# main.net
KiCad netlist of a schematic drawn in Altium Designer
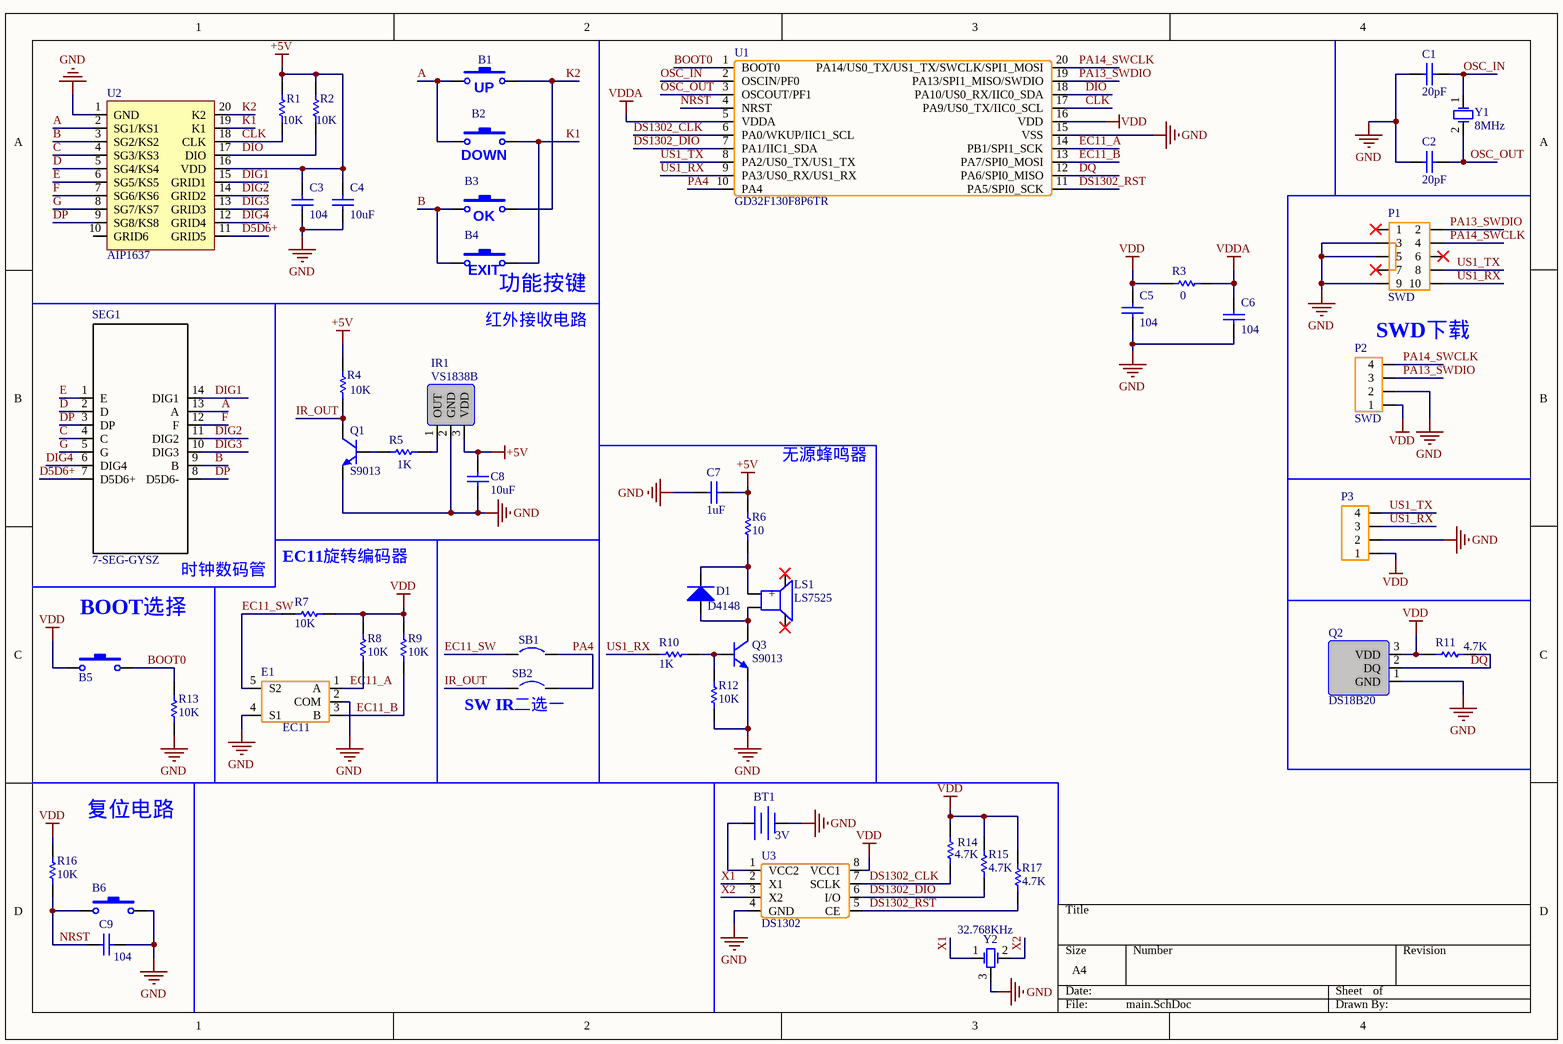
[diagram p0: main.SchDoc]

(export (version "E")
  (design (tool "Eeschema 10.0.6"))
  (components
    (comp (ref "B1")
      (value "用户按钮")
      (footprint "SW-SMD_L6.0-W3.5-LS8.0")
      (description "轻触按钮 - Switch")
      (fields (field (name "PUBLISHER") "Altium Limited"))
      (libsource (lib "ZSF-90") (part "Button"))
    )
    (comp (ref "B2")
      (value "用户按钮")
      (footprint "SW-SMD_L6.0-W3.5-LS8.0")
      (description "轻触按钮 - Switch")
      (fields (field (name "PUBLISHER") "Altium Limited"))
      (libsource (lib "ZSF-90") (part "Button"))
    )
    (comp (ref "B3")
      (value "用户按钮")
      (footprint "SW-SMD_L6.0-W3.5-LS8.0")
      (description "轻触按钮 - Switch")
      (fields (field (name "PUBLISHER") "Altium Limited"))
      (libsource (lib "ZSF-90") (part "Button"))
    )
    (comp (ref "B4")
      (value "用户按钮")
      (footprint "SW-SMD_L6.0-W3.5-LS8.0")
      (description "轻触按钮 - Switch")
      (fields (field (name "PUBLISHER") "Altium Limited"))
      (libsource (lib "ZSF-90") (part "Button"))
    )
    (comp (ref "B5")
      (value "复位按钮")
      (footprint "SW-SMD_L6.0-W3.5-LS8.0")
      (description "轻触按钮 - Switch")
      (fields (field (name "PUBLISHER") "Altium Limited"))
      (libsource (lib "ZSF-90") (part "Button"))
    )
    (comp (ref "B6")
      (value "复位按钮")
      (footprint "SW-SMD_L6.0-W3.5-LS8.0")
      (description "轻触按钮 - Switch")
      (fields (field (name "PUBLISHER") "Altium Limited"))
      (libsource (lib "ZSF-90") (part "Button"))
    )
    (comp (ref "BT1")
      (value "3V")
      (footprint "BAT-SMD_CR1220-2")
      (description "电池")
      (libsource (lib "ZSF-90") (part "Battery"))
    )
    (comp (ref "C1")
      (value "20pF")
      (footprint "C0603")
      (description "无极性电容")
      (fields (field (name "Comment") "Cap") (field (name "PUBLISHER") "信念D力量"))
      (libsource (lib "ZSF-90") (part "Cap"))
    )
    (comp (ref "C2")
      (value "20pF")
      (footprint "C0603")
      (description "无极性电容")
      (fields (field (name "Comment") "Cap") (field (name "PUBLISHER") "信念D力量"))
      (libsource (lib "ZSF-90") (part "Cap"))
    )
    (comp (ref "C3")
      (value "104")
      (footprint "C0603")
      (description "无极性电容")
      (fields (field (name "Comment") "Cap") (field (name "PUBLISHER") "信念D力量"))
      (libsource (lib "ZSF-90") (part "Cap"))
    )
    (comp (ref "C4")
      (value "10uF")
      (footprint "C1812")
      (description "无极性电容")
      (fields (field (name "Comment") "Cap") (field (name "PUBLISHER") "信念D力量"))
      (libsource (lib "ZSF-90") (part "Cap"))
    )
    (comp (ref "C5")
      (value "104")
      (footprint "C0603")
      (description "无极性电容")
      (fields (field (name "Comment") "Cap") (field (name "PUBLISHER") "信念D力量"))
      (libsource (lib "ZSF-90") (part "Cap"))
    )
    (comp (ref "C6")
      (value "104")
      (footprint "C0603")
      (description "无极性电容")
      (fields (field (name "Comment") "Cap") (field (name "PUBLISHER") "信念D力量"))
      (libsource (lib "ZSF-90") (part "Cap"))
    )
    (comp (ref "C7")
      (value "1uF")
      (footprint "C1206")
      (description "无极性电容")
      (fields (field (name "Comment") "Cap") (field (name "PUBLISHER") "信念D力量"))
      (libsource (lib "ZSF-90") (part "Cap"))
    )
    (comp (ref "C8")
      (value "10uF")
      (footprint "C1210")
      (description "无极性电容")
      (fields (field (name "Comment") "Cap") (field (name "PUBLISHER") "信念D力量"))
      (libsource (lib "ZSF-90") (part "Cap"))
    )
    (comp (ref "C9")
      (value "104")
      (footprint "C0603")
      (description "无极性电容")
      (fields (field (name "Comment") "Cap") (field (name "PUBLISHER") "信念D力量"))
      (libsource (lib "ZSF-90") (part "Cap"))
    )
    (comp (ref "D1")
      (value "D4148")
      (footprint "SOD-80_L3.5-W1.5-RD")
      (description "4148二极管")
      (libsource (lib "ZSF-90") (part "D4148"))
    )
    (comp (ref "E1")
      (value "EC11")
      (footprint "EC11")
      (description "EC11 旋转编码器，一圈20个脉冲")
      (libsource (lib "ZSF-90") (part "EC11"))
    )
    (comp (ref "IR1")
      (value "VS1838B")
      (footprint "HS0038")
      (description "红外接收管")
      (libsource (lib "ZSF-90") (part "VS1838B"))
    )
    (comp (ref "LS1")
      (value "LS7525")
      (footprint "BUZ-SMD_4P-7525")
      (description "扬声器 - Loudspeaker")
      (fields (field (name "PUBLISHER") "Altium Limited"))
      (libsource (lib "ZSF-90") (part "LS7525"))
    )
    (comp (ref "P1")
      (value "SWD")
      (footprint "IDC-SMD-10P-1.27MM")
      (description "牛角座")
      (libsource (lib "ZSF-90") (part "IDC-2x5"))
    )
    (comp (ref "P2")
      (value "SWD")
      (footprint "HDR1X4-Male")
      (description "排针，2.54MM")
      (libsource (lib "ZSF-90") (part "HDR-M-2.54-1x4"))
    )
    (comp (ref "P3")
      (value "HDR-M-2.54-1x4")
      (footprint "HDR1X4-Male")
      (description "排针，2.54MM")
      (libsource (lib "ZSF-90") (part "HDR-M-2.54-1x4"))
    )
    (comp (ref "Q1")
      (value "S9013")
      (footprint "SOT-23-3_L2.9-W1.6-P1.90-LS2.8-BR")
      (description "NPN 三极管")
      (libsource (lib "ZSF-90") (part "S9013"))
    )
    (comp (ref "Q2")
      (value "DS18B20")
      (footprint "TO-92A")
      (description "温度传感器")
      (libsource (lib "ZSF-90") (part "DS18B20"))
    )
    (comp (ref "Q3")
      (value "S9013")
      (footprint "SOT-23-3_L2.9-W1.6-P1.90-LS2.8-BR")
      (description "NPN 三极管")
      (libsource (lib "ZSF-90") (part "S9013"))
    )
    (comp (ref "R1")
      (value "10K")
      (footprint "R0603")
      (description "美国电阻符号")
      (fields (field (name "Comment") "Res") (field (name "PUBLISHER") "Altium Limited"))
      (libsource (lib "ZSF-90") (part "Res"))
    )
    (comp (ref "R2")
      (value "10K")
      (footprint "R0603")
      (description "美国电阻符号")
      (fields (field (name "Comment") "Res") (field (name "PUBLISHER") "Altium Limited"))
      (libsource (lib "ZSF-90") (part "Res"))
    )
    (comp (ref "R3")
      (value "0")
      (footprint "R0603")
      (description "美国电阻符号")
      (fields (field (name "Comment") "Res") (field (name "PUBLISHER") "Altium Limited"))
      (libsource (lib "ZSF-90") (part "Res"))
    )
    (comp (ref "R4")
      (value "10K")
      (footprint "R0603")
      (description "美国电阻符号")
      (fields (field (name "Comment") "Res") (field (name "PUBLISHER") "Altium Limited"))
      (libsource (lib "ZSF-90") (part "Res"))
    )
    (comp (ref "R5")
      (value "1K")
      (footprint "R0603")
      (description "美国电阻符号")
      (fields (field (name "Comment") "Res") (field (name "PUBLISHER") "Altium Limited"))
      (libsource (lib "ZSF-90") (part "Res"))
    )
    (comp (ref "R6")
      (value "10")
      (footprint "R0603")
      (description "美国电阻符号")
      (fields (field (name "Comment") "Res") (field (name "PUBLISHER") "Altium Limited"))
      (libsource (lib "ZSF-90") (part "Res"))
    )
    (comp (ref "R7")
      (value "10K")
      (footprint "R0603")
      (description "美国电阻符号")
      (fields (field (name "Comment") "Res") (field (name "PUBLISHER") "Altium Limited"))
      (libsource (lib "ZSF-90") (part "Res"))
    )
    (comp (ref "R8")
      (value "10K")
      (footprint "R0603")
      (description "美国电阻符号")
      (fields (field (name "Comment") "Res") (field (name "PUBLISHER") "Altium Limited"))
      (libsource (lib "ZSF-90") (part "Res"))
    )
    (comp (ref "R9")
      (value "10K")
      (footprint "R0603")
      (description "美国电阻符号")
      (fields (field (name "Comment") "Res") (field (name "PUBLISHER") "Altium Limited"))
      (libsource (lib "ZSF-90") (part "Res"))
    )
    (comp (ref "R10")
      (value "1K")
      (footprint "R0603")
      (description "美国电阻符号")
      (fields (field (name "Comment") "Res") (field (name "PUBLISHER") "Altium Limited"))
      (libsource (lib "ZSF-90") (part "Res"))
    )
    (comp (ref "R11")
      (value "4.7K")
      (footprint "R0603")
      (description "美国电阻符号")
      (fields (field (name "Comment") "Res") (field (name "PUBLISHER") "Altium Limited"))
      (libsource (lib "ZSF-90") (part "Res"))
    )
    (comp (ref "R12")
      (value "10K")
      (footprint "R0603")
      (description "美国电阻符号")
      (fields (field (name "Comment") "Res") (field (name "PUBLISHER") "Altium Limited"))
      (libsource (lib "ZSF-90") (part "Res"))
    )
    (comp (ref "R13")
      (value "10K")
      (footprint "R0603")
      (description "美国电阻符号")
      (fields (field (name "Comment") "Res") (field (name "PUBLISHER") "Altium Limited"))
      (libsource (lib "ZSF-90") (part "Res"))
    )
    (comp (ref "R14")
      (value "4.7K")
      (footprint "R0603")
      (description "美国电阻符号")
      (fields (field (name "Comment") "Res") (field (name "PUBLISHER") "Altium Limited"))
      (libsource (lib "ZSF-90") (part "Res"))
    )
    (comp (ref "R15")
      (value "4.7K")
      (footprint "R0603")
      (description "美国电阻符号")
      (fields (field (name "Comment") "Res") (field (name "PUBLISHER") "Altium Limited"))
      (libsource (lib "ZSF-90") (part "Res"))
    )
    (comp (ref "R16")
      (value "10K")
      (footprint "R0603")
      (description "美国电阻符号")
      (fields (field (name "Comment") "Res") (field (name "PUBLISHER") "Altium Limited"))
      (libsource (lib "ZSF-90") (part "Res"))
    )
    (comp (ref "R17")
      (value "4.7K")
      (footprint "R0603")
      (description "美国电阻符号")
      (fields (field (name "Comment") "Res") (field (name "PUBLISHER") "Altium Limited"))
      (libsource (lib "ZSF-90") (part "Res"))
    )
    (comp (ref "SB1")
      (value "Circuit Breaker")
      (footprint "JP2_SMD")
      (description "断路器 短路选择 - Circuit Breaker")
      (fields (field (name "PUBLISHER") "Altium Limited"))
      (libsource (lib "ZSF-90") (part "Circuit Breaker"))
    )
    (comp (ref "SB2")
      (value "Circuit Breaker")
      (footprint "JP2_SMD")
      (description "断路器 短路选择 - Circuit Breaker")
      (fields (field (name "PUBLISHER") "Altium Limited"))
      (libsource (lib "ZSF-90") (part "Circuit Breaker"))
    )
    (comp (ref "SEG1")
      (value "7-SEG-GYSZ")
      (footprint "7-SEG-GY0_8INCH")
      (description "4位共阳极数码管 带时钟显示")
      (libsource (lib "ZSF-90") (part "7-SEG-GYSZ"))
    )
    (comp (ref "U1")
      (value "GD32F130F8P6TR")
      (footprint "TSSOP-20-N")
      (description "GD32单片机 RAM 8KB Flash 64KB")
      (libsource (lib "ZSF-90") (part "GD32F130F8P6TR"))
    )
    (comp (ref "U2")
      (value "AIP1637")
      (footprint "SOP-20_L12.8-W7.5-P1.27-LS10.4-BL")
      (description "数码管驱动")
      (libsource (lib "ZSF-90") (part "AIP1637"))
    )
    (comp (ref "U3")
      (value "DS1302")
      (footprint "SOIC-8_208mil_L5.3-W5.3-P1.27-LS8.0-BL")
      (description "时钟芯片")
      (libsource (lib "ZSF-90") (part "DS1302"))
    )
    (comp (ref "Y1")
      (value "8MHz")
      (footprint "HC-49")
      (description "晶振 - Crystal Oscillator")
      (fields (field (name "PUBLISHER") "Altium Limited"))
      (libsource (lib "ZSF-90") (part "XTAL"))
    )
    (comp (ref "Y2")
      (value "32.768KHz")
      (footprint "CRYSTAL-SMD_BD2.0-L6.0-P2.54-32.768")
      (description "晶振 - Crystal Oscillator")
      (fields (field (name "PUBLISHER") "Altium Limited"))
      (libsource (lib "ZSF-90") (part "XTAL-3"))
    )
  )
  (nets
    (net (code "1") (name "+5V") (class "Default")
      (node (ref "C3") (pin "2") (pinfunction "2_2") (pintype "passive"))
      (node (ref "C4") (pin "2") (pinfunction "2_2") (pintype "passive"))
      (node (ref "C7") (pin "1") (pinfunction "1_1") (pintype "passive"))
      (node (ref "C8") (pin "1") (pinfunction "1_1") (pintype "passive"))
      (node (ref "IR1") (pin "3") (pinfunction "VDD_3") (pintype "passive"))
      (node (ref "R1") (pin "2") (pinfunction "2_2") (pintype "passive"))
      (node (ref "R2") (pin "2") (pinfunction "2_2") (pintype "passive"))
      (node (ref "R4") (pin "1") (pinfunction "1_1") (pintype "passive"))
      (node (ref "R6") (pin "2") (pinfunction "2_2") (pintype "passive"))
      (node (ref "U2") (pin "16") (pinfunction "VDD_16") (pintype "passive"))
    )
    (net (code "2") (name "/A") (class "Default")
      (node (ref "B1") (pin "1") (pinfunction "1_1") (pintype "passive"))
      (node (ref "B2") (pin "1") (pinfunction "1_1") (pintype "passive"))
      (node (ref "SEG1") (pin "13") (pinfunction "A_13") (pintype "passive"))
      (node (ref "U2") (pin "2") (pinfunction "SG1/KS1_2") (pintype "passive"))
    )
    (net (code "3") (name "/B") (class "Default")
      (node (ref "B3") (pin "1") (pinfunction "1_1") (pintype "passive"))
      (node (ref "B4") (pin "1") (pinfunction "1_1") (pintype "passive"))
      (node (ref "SEG1") (pin "9") (pinfunction "B_9") (pintype "passive"))
      (node (ref "U2") (pin "3") (pinfunction "SG2/KS2_3") (pintype "passive"))
    )
    (net (code "4") (name "/BOOT0") (class "Default")
      (node (ref "B5") (pin "2") (pinfunction "2_2") (pintype "passive"))
      (node (ref "R13") (pin "2") (pinfunction "2_2") (pintype "passive"))
      (node (ref "U1") (pin "1") (pinfunction "BOOT0_1") (pintype "passive"))
    )
    (net (code "5") (name "/C") (class "Default")
      (node (ref "SEG1") (pin "4") (pinfunction "C_4") (pintype "passive"))
      (node (ref "U2") (pin "4") (pinfunction "SG3/KS3_4") (pintype "passive"))
    )
    (net (code "6") (name "/CLK") (class "Default")
      (node (ref "R1") (pin "1") (pinfunction "1_1") (pintype "passive"))
      (node (ref "U1") (pin "17") (pinfunction "PA9/US0_TX/IIC0_SCL_17") (pintype "passive"))
      (node (ref "U2") (pin "18") (pinfunction "CLK_18") (pintype "passive"))
    )
    (net (code "7") (name "/D") (class "Default")
      (node (ref "SEG1") (pin "2") (pinfunction "D_2") (pintype "passive"))
      (node (ref "U2") (pin "5") (pinfunction "SG4/KS4_5") (pintype "passive"))
    )
    (net (code "8") (name "/D5D6+") (class "Default")
      (node (ref "SEG1") (pin "7") (pinfunction "D5D6+_7") (pintype "passive"))
      (node (ref "U2") (pin "11") (pinfunction "GRID5_11") (pintype "passive"))
    )
    (net (code "9") (name "/DIG1") (class "Default")
      (node (ref "SEG1") (pin "14") (pinfunction "DIG1_14") (pintype "passive"))
      (node (ref "U2") (pin "15") (pinfunction "GRID1_15") (pintype "passive"))
    )
    (net (code "10") (name "/DIG2") (class "Default")
      (node (ref "SEG1") (pin "11") (pinfunction "DIG2_11") (pintype "passive"))
      (node (ref "U2") (pin "14") (pinfunction "GRID2_14") (pintype "passive"))
    )
    (net (code "11") (name "/DIG3") (class "Default")
      (node (ref "SEG1") (pin "10") (pinfunction "DIG3_10") (pintype "passive"))
      (node (ref "U2") (pin "13") (pinfunction "GRID3_13") (pintype "passive"))
    )
    (net (code "12") (name "/DIG4") (class "Default")
      (node (ref "SEG1") (pin "6") (pinfunction "DIG4_6") (pintype "passive"))
      (node (ref "U2") (pin "12") (pinfunction "GRID4_12") (pintype "passive"))
    )
    (net (code "13") (name "/DIO") (class "Default")
      (node (ref "R2") (pin "1") (pinfunction "1_1") (pintype "passive"))
      (node (ref "U1") (pin "18") (pinfunction "PA10/US0_RX/IIC0_SDA_18") (pintype "passive"))
      (node (ref "U2") (pin "17") (pinfunction "DIO_17") (pintype "passive"))
    )
    (net (code "14") (name "/DP") (class "Default")
      (node (ref "SEG1") (pin "3") (pinfunction "DP_3") (pintype "passive"))
      (node (ref "SEG1") (pin "8") (pinfunction "D5D6-_8") (pintype "passive"))
      (node (ref "U2") (pin "9") (pinfunction "SG8/KS8_9") (pintype "passive"))
    )
    (net (code "15") (name "/DQ") (class "Default")
      (node (ref "Q2") (pin "2") (pinfunction "DQ_2") (pintype "passive"))
      (node (ref "R11") (pin "1") (pinfunction "1_1") (pintype "passive"))
      (node (ref "U1") (pin "12") (pinfunction "PA6/SPI0_MISO_12") (pintype "passive"))
    )
    (net (code "16") (name "/DS1302_CLK") (class "Default")
      (node (ref "R14") (pin "2") (pinfunction "2_2") (pintype "passive"))
      (node (ref "U1") (pin "6") (pinfunction "PA0/WKUP/IIC1_SCL_6") (pintype "passive"))
      (node (ref "U3") (pin "7") (pinfunction "SCLK_7") (pintype "passive"))
    )
    (net (code "17") (name "/DS1302_DIO") (class "Default")
      (node (ref "R15") (pin "2") (pinfunction "2_2") (pintype "passive"))
      (node (ref "U1") (pin "7") (pinfunction "PA1/IIC1_SDA_7") (pintype "passive"))
      (node (ref "U3") (pin "6") (pinfunction "I/O_6") (pintype "passive"))
    )
    (net (code "18") (name "/DS1302_RST") (class "Default")
      (node (ref "R17") (pin "2") (pinfunction "2_2") (pintype "passive"))
      (node (ref "U1") (pin "11") (pinfunction "PA5/SPI0_SCK_11") (pintype "passive"))
      (node (ref "U3") (pin "5") (pinfunction "CE_5") (pintype "passive"))
    )
    (net (code "19") (name "/E") (class "Default")
      (node (ref "SEG1") (pin "1") (pinfunction "E_1") (pintype "passive"))
      (node (ref "U2") (pin "6") (pinfunction "SG5/KS5_6") (pintype "passive"))
    )
    (net (code "20") (name "/EC11_A") (class "Default")
      (node (ref "E1") (pin "1") (pinfunction "A_1") (pintype "passive"))
      (node (ref "R8") (pin "1") (pinfunction "1_1") (pintype "passive"))
      (node (ref "U1") (pin "14") (pinfunction "PB1/SPI1_SCK_14") (pintype "passive"))
    )
    (net (code "21") (name "/EC11_B") (class "Default")
      (node (ref "E1") (pin "3") (pinfunction "B_3") (pintype "passive"))
      (node (ref "R9") (pin "1") (pinfunction "1_1") (pintype "passive"))
      (node (ref "U1") (pin "13") (pinfunction "PA7/SPI0_MOSI_13") (pintype "passive"))
    )
    (net (code "22") (name "/EC11_SW") (class "Default")
      (node (ref "E1") (pin "5") (pinfunction "S2_5") (pintype "passive"))
      (node (ref "R7") (pin "2") (pinfunction "2_2") (pintype "passive"))
      (node (ref "SB1") (pin "1") (pinfunction "1_1") (pintype "passive"))
    )
    (net (code "23") (name "/F") (class "Default")
      (node (ref "SEG1") (pin "12") (pinfunction "F_12") (pintype "passive"))
      (node (ref "U2") (pin "7") (pinfunction "SG6/KS6_7") (pintype "passive"))
    )
    (net (code "24") (name "/G") (class "Default")
      (node (ref "SEG1") (pin "5") (pinfunction "G_5") (pintype "passive"))
      (node (ref "U2") (pin "8") (pinfunction "SG7/KS7_8") (pintype "passive"))
    )
    (net (code "25") (name "/IR_OUT") (class "Default")
      (node (ref "Q1") (pin "3") (pinfunction "C_3") (pintype "passive"))
      (node (ref "R4") (pin "2") (pinfunction "2_2") (pintype "passive"))
      (node (ref "SB2") (pin "1") (pinfunction "1_1") (pintype "passive"))
    )
    (net (code "26") (name "/K1") (class "Default")
      (node (ref "B2") (pin "2") (pinfunction "2_2") (pintype "passive"))
      (node (ref "B4") (pin "2") (pinfunction "2_2") (pintype "passive"))
      (node (ref "U2") (pin "19") (pinfunction "K1_19") (pintype "passive"))
    )
    (net (code "27") (name "/K2") (class "Default")
      (node (ref "B1") (pin "2") (pinfunction "2_2") (pintype "passive"))
      (node (ref "B3") (pin "2") (pinfunction "2_2") (pintype "passive"))
      (node (ref "U2") (pin "20") (pinfunction "K2_20") (pintype "passive"))
    )
    (net (code "28") (name "/NRST") (class "Default")
      (node (ref "B6") (pin "1") (pinfunction "1_1") (pintype "passive"))
      (node (ref "C9") (pin "1") (pinfunction "1_1") (pintype "passive"))
      (node (ref "R16") (pin "1") (pinfunction "1_1") (pintype "passive"))
      (node (ref "U1") (pin "4") (pinfunction "NRST_4") (pintype "passive"))
    )
    (net (code "29") (name "/OSC_IN") (class "Default")
      (node (ref "C1") (pin "2") (pinfunction "2_2") (pintype "passive"))
      (node (ref "U1") (pin "2") (pinfunction "OSCIN/PF0_2") (pintype "passive"))
      (node (ref "Y1") (pin "1") (pinfunction "OSC1_1") (pintype "passive"))
    )
    (net (code "30") (name "/OSC_OUT") (class "Default")
      (node (ref "C2") (pin "2") (pinfunction "2_2") (pintype "passive"))
      (node (ref "U1") (pin "3") (pinfunction "OSCOUT/PF1_3") (pintype "passive"))
      (node (ref "Y1") (pin "2") (pinfunction "OSC2_2") (pintype "passive"))
    )
    (net (code "31") (name "/PA4") (class "Default")
      (node (ref "SB1") (pin "2") (pinfunction "2_2") (pintype "passive"))
      (node (ref "SB2") (pin "2") (pinfunction "2_2") (pintype "passive"))
      (node (ref "U1") (pin "10") (pinfunction "PA4_10") (pintype "passive"))
    )
    (net (code "32") (name "/PA13_SWDIO") (class "Default")
      (node (ref "P1") (pin "2") (pinfunction "2_2") (pintype "passive"))
      (node (ref "P2") (pin "3") (pinfunction "3_3") (pintype "passive"))
      (node (ref "U1") (pin "19") (pinfunction "PA13/SPI1_MISO/SWDIO_19") (pintype "passive"))
    )
    (net (code "33") (name "/PA14_SWCLK") (class "Default")
      (node (ref "P1") (pin "4") (pinfunction "4_4") (pintype "passive"))
      (node (ref "P2") (pin "4") (pinfunction "4_4") (pintype "passive"))
      (node (ref "U1") (pin "20") (pinfunction "PA14/US0_TX/US1_TX/SWCLK/SPI1_MOSI_20") (pintype "passive"))
    )
    (net (code "34") (name "/US1_RX") (class "Default")
      (node (ref "P1") (pin "10") (pinfunction "10_10") (pintype "passive"))
      (node (ref "P3") (pin "3") (pinfunction "3_3") (pintype "passive"))
      (node (ref "R10") (pin "2") (pinfunction "2_2") (pintype "passive"))
      (node (ref "U1") (pin "9") (pinfunction "PA3/US0_RX/US1_RX_9") (pintype "passive"))
    )
    (net (code "35") (name "/US1_TX") (class "Default")
      (node (ref "P1") (pin "8") (pinfunction "8_8") (pintype "passive"))
      (node (ref "P3") (pin "4") (pinfunction "4_4") (pintype "passive"))
      (node (ref "U1") (pin "8") (pinfunction "PA2/US0_TX/US1_TX_8") (pintype "passive"))
    )
    (net (code "36") (name "/X1") (class "Default")
      (node (ref "U3") (pin "2") (pinfunction "X1_2") (pintype "passive"))
      (node (ref "Y2") (pin "1") (pinfunction "OSC1_1") (pintype "passive"))
    )
    (net (code "37") (name "/X2") (class "Default")
      (node (ref "U3") (pin "3") (pinfunction "X2_3") (pintype "passive"))
      (node (ref "Y2") (pin "2") (pinfunction "OSC2_2") (pintype "passive"))
    )
    (net (code "38") (name "GND") (class "Default")
      (node (ref "B6") (pin "2") (pinfunction "2_2") (pintype "passive"))
      (node (ref "BT1") (pin "2") (pinfunction "-_2") (pintype "passive"))
      (node (ref "C1") (pin "1") (pinfunction "1_1") (pintype "passive"))
      (node (ref "C2") (pin "1") (pinfunction "1_1") (pintype "passive"))
      (node (ref "C3") (pin "1") (pinfunction "1_1") (pintype "passive"))
      (node (ref "C4") (pin "1") (pinfunction "1_1") (pintype "passive"))
      (node (ref "C5") (pin "1") (pinfunction "1_1") (pintype "passive"))
      (node (ref "C6") (pin "1") (pinfunction "1_1") (pintype "passive"))
      (node (ref "C7") (pin "2") (pinfunction "2_2") (pintype "passive"))
      (node (ref "C8") (pin "2") (pinfunction "2_2") (pintype "passive"))
      (node (ref "C9") (pin "2") (pinfunction "2_2") (pintype "passive"))
      (node (ref "E1") (pin "2") (pinfunction "COM_2") (pintype "passive"))
      (node (ref "E1") (pin "4") (pinfunction "S1_4") (pintype "passive"))
      (node (ref "IR1") (pin "2") (pinfunction "GND_2") (pintype "passive"))
      (node (ref "P1") (pin "3") (pinfunction "3_3") (pintype "passive"))
      (node (ref "P1") (pin "5") (pinfunction "5_5") (pintype "passive"))
      (node (ref "P1") (pin "9") (pinfunction "9_9") (pintype "passive"))
      (node (ref "P2") (pin "2") (pinfunction "2_2") (pintype "passive"))
      (node (ref "P3") (pin "2") (pinfunction "2_2") (pintype "passive"))
      (node (ref "Q1") (pin "2") (pinfunction "E_2") (pintype "passive"))
      (node (ref "Q2") (pin "1") (pinfunction "GND_1") (pintype "passive"))
      (node (ref "Q3") (pin "2") (pinfunction "E_2") (pintype "passive"))
      (node (ref "R12") (pin "2") (pinfunction "2_2") (pintype "passive"))
      (node (ref "R13") (pin "1") (pinfunction "1_1") (pintype "passive"))
      (node (ref "U1") (pin "15") (pinfunction "VSS_15") (pintype "passive"))
      (node (ref "U2") (pin "1") (pinfunction "GND_1") (pintype "passive"))
      (node (ref "U3") (pin "4") (pinfunction "GND_4") (pintype "passive"))
      (node (ref "Y2") (pin "3") (pinfunction "GND_3") (pintype "passive"))
    )
    (net (code "39") (name "Net-(BT1-+)") (class "Default")
      (node (ref "BT1") (pin "1") (pinfunction "+_1") (pintype "passive"))
      (node (ref "U3") (pin "1") (pinfunction "VCC2_1") (pintype "passive"))
    )
    (net (code "40") (name "Net-(D1-A)") (class "Default")
      (node (ref "D1") (pin "2") (pinfunction "A_2") (pintype "passive"))
      (node (ref "LS1") (pin "2") (pinfunction "-_2") (pintype "passive"))
      (node (ref "Q3") (pin "3") (pinfunction "C_3") (pintype "passive"))
    )
    (net (code "41") (name "Net-(D1-K)") (class "Default")
      (node (ref "D1") (pin "1") (pinfunction "K_1") (pintype "passive"))
      (node (ref "LS1") (pin "1") (pinfunction "+_1") (pintype "passive"))
      (node (ref "R6") (pin "1") (pinfunction "1_1") (pintype "passive"))
    )
    (net (code "42") (name "Net-(IR1-OUT)") (class "Default")
      (node (ref "IR1") (pin "1") (pinfunction "OUT_1") (pintype "passive"))
      (node (ref "R5") (pin "1") (pinfunction "1_1") (pintype "passive"))
    )
    (net (code "43") (name "Net-(Q1-B)") (class "Default")
      (node (ref "Q1") (pin "1") (pinfunction "B_1") (pintype "passive"))
      (node (ref "R5") (pin "2") (pinfunction "2_2") (pintype "passive"))
    )
    (net (code "44") (name "Net-(Q3-B)") (class "Default")
      (node (ref "Q3") (pin "1") (pinfunction "B_1") (pintype "passive"))
      (node (ref "R10") (pin "1") (pinfunction "1_1") (pintype "passive"))
      (node (ref "R12") (pin "1") (pinfunction "1_1") (pintype "passive"))
    )
    (net (code "45") (name "VDD") (class "Default")
      (node (ref "B5") (pin "1") (pinfunction "1_1") (pintype "passive"))
      (node (ref "C5") (pin "2") (pinfunction "2_2") (pintype "passive"))
      (node (ref "P2") (pin "1") (pinfunction "1_1") (pintype "passive"))
      (node (ref "P3") (pin "1") (pinfunction "1_1") (pintype "passive"))
      (node (ref "Q2") (pin "3") (pinfunction "VDD_3") (pintype "passive"))
      (node (ref "R11") (pin "2") (pinfunction "2_2") (pintype "passive"))
      (node (ref "R14") (pin "1") (pinfunction "1_1") (pintype "passive"))
      (node (ref "R15") (pin "1") (pinfunction "1_1") (pintype "passive"))
      (node (ref "R16") (pin "2") (pinfunction "2_2") (pintype "passive"))
      (node (ref "R17") (pin "1") (pinfunction "1_1") (pintype "passive"))
      (node (ref "R3") (pin "2") (pinfunction "2_2") (pintype "passive"))
      (node (ref "R7") (pin "1") (pinfunction "1_1") (pintype "passive"))
      (node (ref "R8") (pin "2") (pinfunction "2_2") (pintype "passive"))
      (node (ref "R9") (pin "2") (pinfunction "2_2") (pintype "passive"))
      (node (ref "U1") (pin "16") (pinfunction "VDD_16") (pintype "passive"))
      (node (ref "U3") (pin "8") (pinfunction "VCC1_8") (pintype "passive"))
    )
    (net (code "46") (name "VDDA") (class "Default")
      (node (ref "C6") (pin "2") (pinfunction "2_2") (pintype "passive"))
      (node (ref "R3") (pin "1") (pinfunction "1_1") (pintype "passive"))
      (node (ref "U1") (pin "5") (pinfunction "VDDA_5") (pintype "passive"))
    )
    (net (code "47") (name "unconnected-(LS1-Pad3)") (class "Default")
      (node (ref "LS1") (pin "3") (pinfunction "3_3") (pintype "passive+no_connect"))
    )
    (net (code "48") (name "unconnected-(LS1-Pad4)") (class "Default")
      (node (ref "LS1") (pin "4") (pinfunction "4_4") (pintype "passive+no_connect"))
    )
    (net (code "49") (name "unconnected-(P1-Pad1)") (class "Default")
      (node (ref "P1") (pin "1") (pinfunction "1_1") (pintype "passive+no_connect"))
    )
    (net (code "50") (name "unconnected-(P1-Pad6)") (class "Default")
      (node (ref "P1") (pin "6") (pinfunction "6_6") (pintype "passive+no_connect"))
    )
    (net (code "51") (name "unconnected-(P1-Pad7)") (class "Default")
      (node (ref "P1") (pin "7") (pinfunction "7_7") (pintype "passive+no_connect"))
    )
    (net (code "52") (name "unconnected-(U2-GRID6-Pad10)") (class "Default")
      (node (ref "U2") (pin "10") (pinfunction "GRID6_10") (pintype "passive"))
    )
  )
)
